# WirelessEarBuds_PhotoHall.net
KiCad netlist of a schematic drawn in Altium Designer
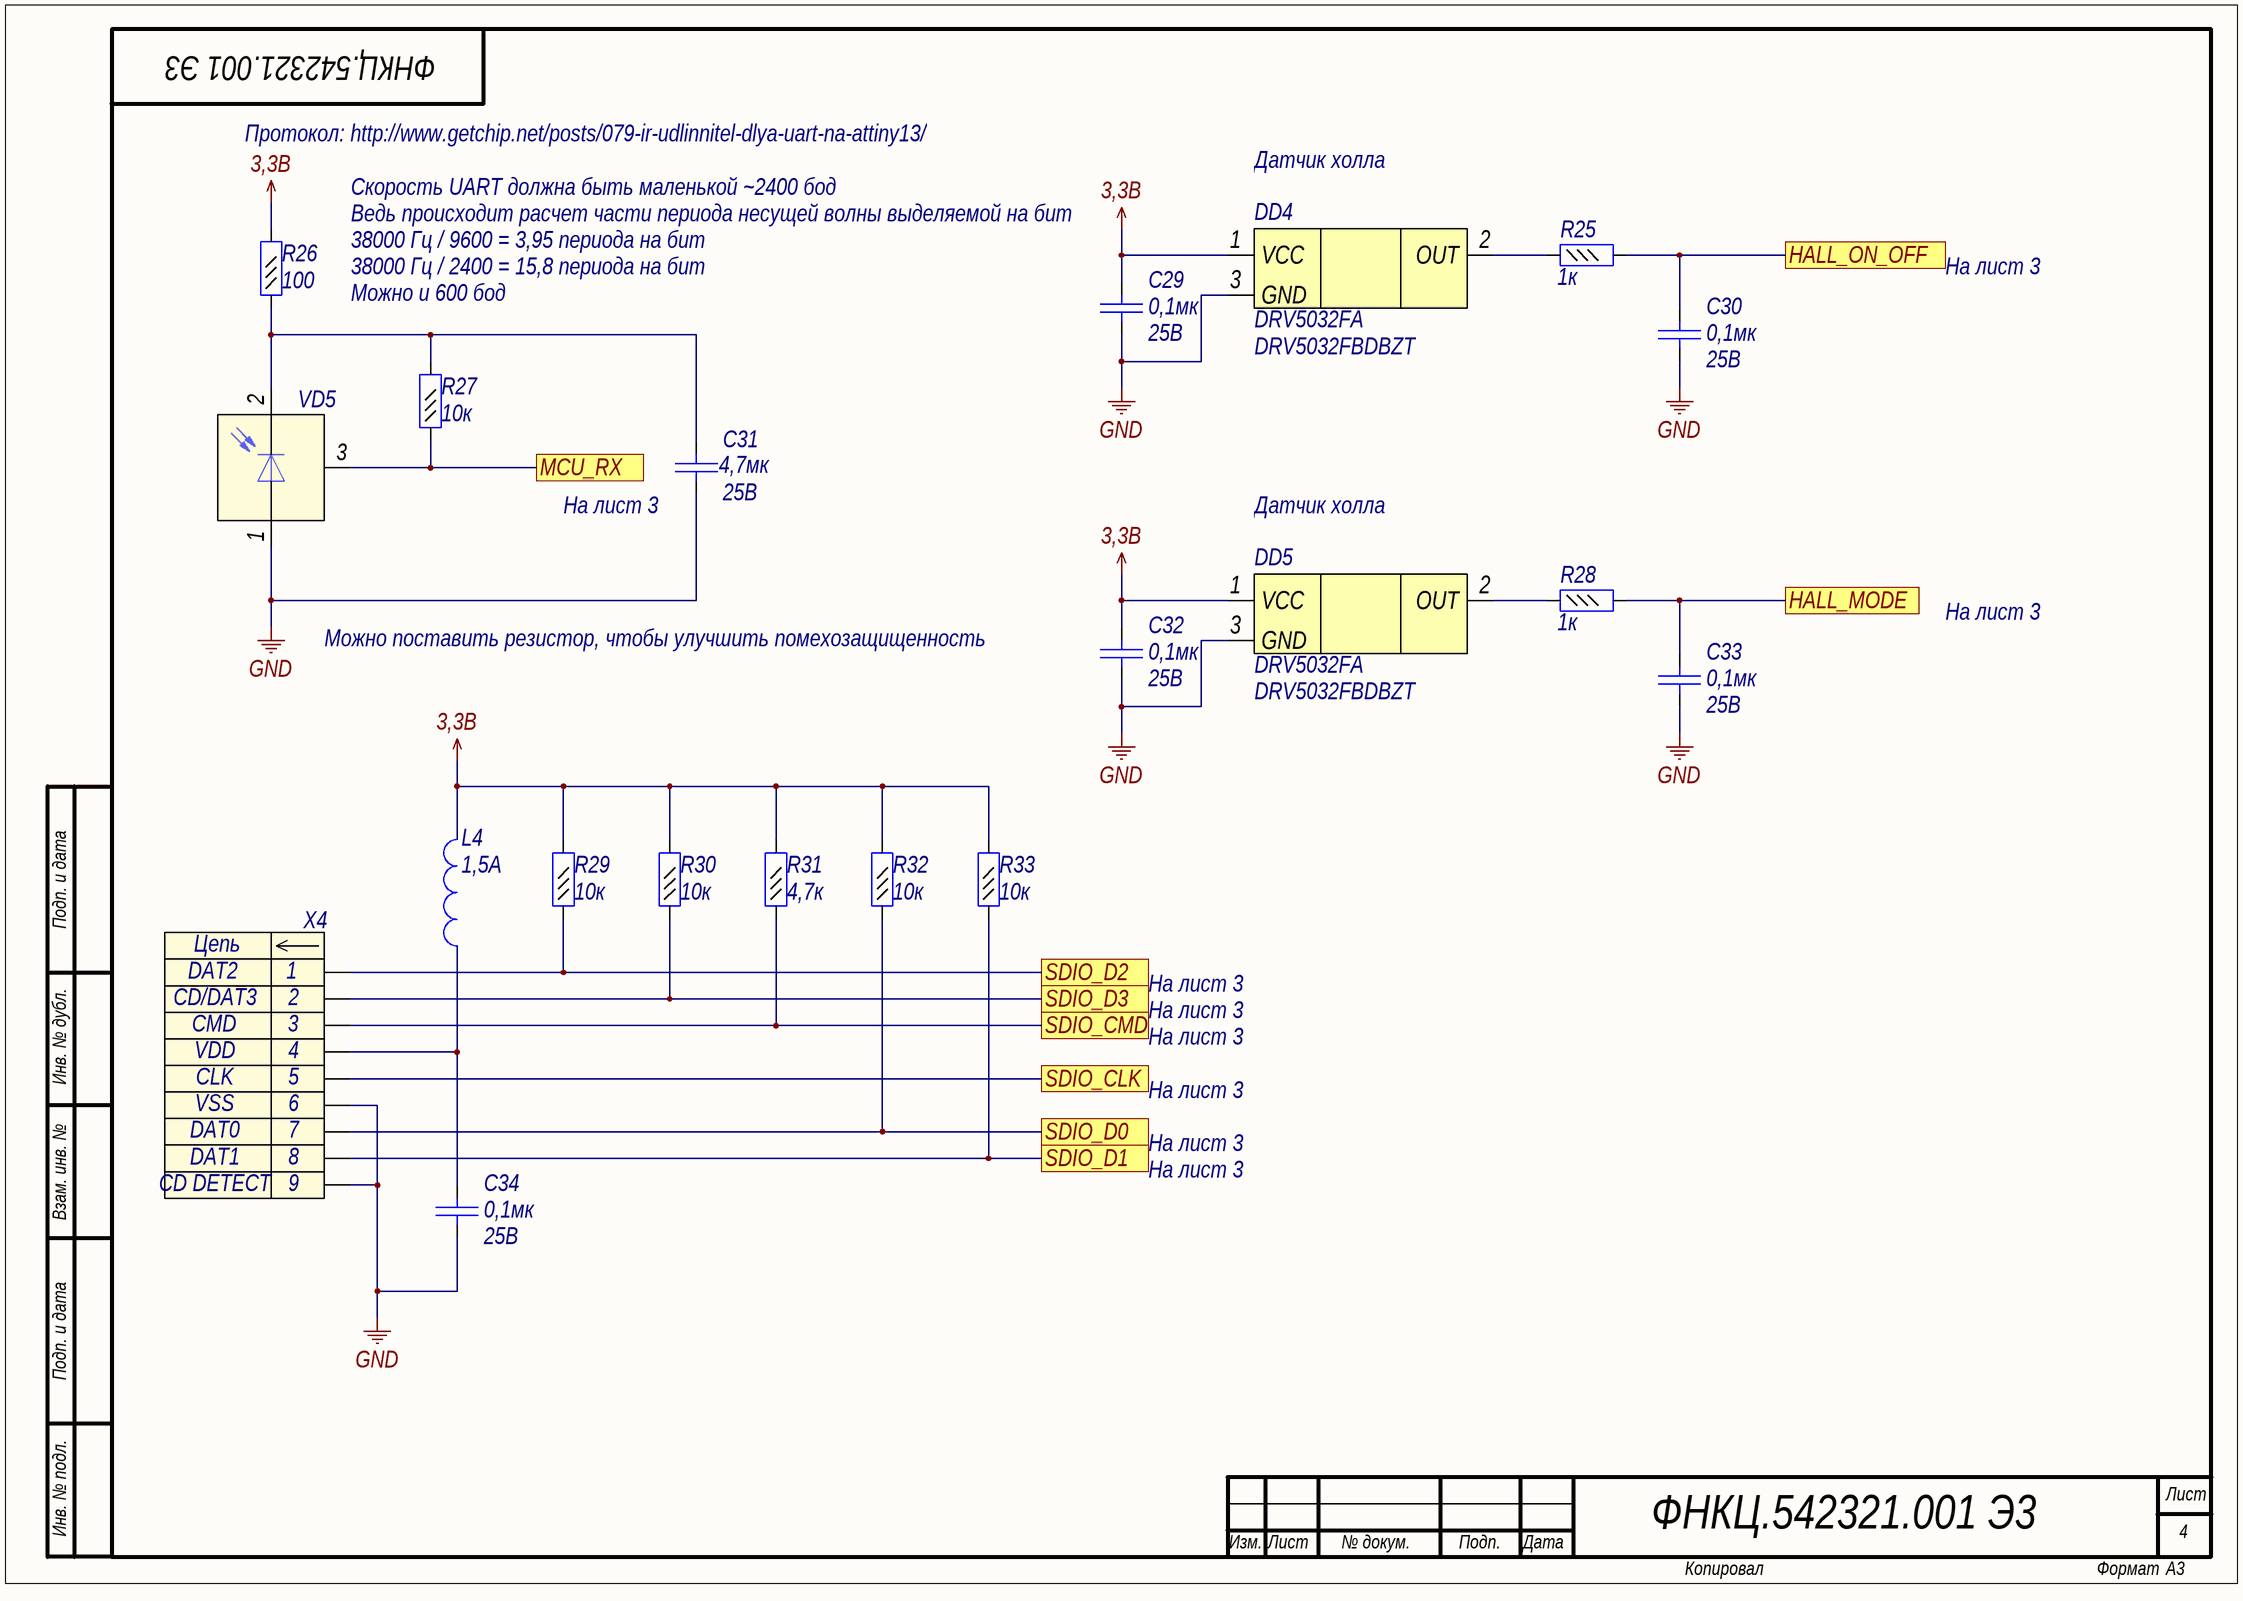
[diagram p0: WirelessEarBuds_PhotoHall.SchDoc]

(export (version "E")
  (design (tool "Eeschema 10.0.6"))
  (components
    (comp (ref "C29")
      (value "0,1мк")
      (footprint "C0402")
      (description "Конденсатор")
      (fields
        (field (name "VOLTAGE") "25B")
        (field (name "PART NUMBER") "GRM155F51E104Z**")
        (field (name "Comment") "Capacitor")
      )
      (libsource (lib "MOP44") (part "Capacitor"))
    )
    (comp (ref "C30")
      (value "0,1мк")
      (footprint "C0402")
      (description "Конденсатор")
      (fields
        (field (name "VOLTAGE") "25B")
        (field (name "PART NUMBER") "GRM155F51E104Z**")
        (field (name "Comment") "Capacitor")
      )
      (libsource (lib "MOP44") (part "Capacitor"))
    )
    (comp (ref "C31")
      (value "4,7мк")
      (footprint "C0805")
      (description "Конденсатор")
      (fields
        (field (name "VOLTAGE") "25B")
        (field (name "PART NUMBER") "GRM21BR61E475KA12L")
        (field (name "Comment") "Capacitor")
      )
      (libsource (lib "MOP44") (part "Capacitor"))
    )
    (comp (ref "C32")
      (value "0,1мк")
      (footprint "C0402")
      (description "Конденсатор")
      (fields
        (field (name "VOLTAGE") "25B")
        (field (name "PART NUMBER") "GRM155F51E104Z**")
        (field (name "Comment") "Capacitor")
      )
      (libsource (lib "MOP44") (part "Capacitor"))
    )
    (comp (ref "C33")
      (value "0,1мк")
      (footprint "C0402")
      (description "Конденсатор")
      (fields
        (field (name "VOLTAGE") "25B")
        (field (name "PART NUMBER") "GRM155F51E104Z**")
        (field (name "Comment") "Capacitor")
      )
      (libsource (lib "MOP44") (part "Capacitor"))
    )
    (comp (ref "C34")
      (value "0,1мк")
      (footprint "C0402")
      (description "Конденсатор")
      (fields
        (field (name "VOLTAGE") "25B")
        (field (name "PART NUMBER") "GRM155F51E104Z**")
        (field (name "Comment") "Capacitor")
      )
      (libsource (lib "MOP44") (part "Capacitor"))
    )
    (comp (ref "DD4")
      (value "DRV5032")
      (footprint "SOT23-3")
      (description "Датчик Холла с рекордно низким потреблением")
      (fields (field (name "PART NUMBER") "DRV5032FA"))
      (libsource (lib "MOP44") (part "DRV5032"))
    )
    (comp (ref "DD5")
      (value "DRV5032")
      (footprint "SOT23-3")
      (description "Датчик Холла с рекордно низким потреблением")
      (fields (field (name "PART NUMBER") "DRV5032FA"))
      (libsource (lib "MOP44") (part "DRV5032"))
    )
    (comp (ref "L4")
      (value "Inductor")
      (footprint "L0603")
      (description "EMI Suppression Filter")
      (fields (field (name "RATED CURRENT") "1,5A") (field (name "PART NUMBER") "BLM18PG181SN1D"))
      (libsource (lib "MOP44") (part "Inductor"))
    )
    (comp (ref "R25")
      (value "1к")
      (footprint "R0402")
      (description "Резистор")
      (fields (field (name "PART NUMBER") "RC0402FR-071KL") (field (name "POWER") "0,062Вт"))
      (libsource (lib "") (part "Resistor_0,062Вт_1"))
    )
    (comp (ref "R26")
      (value "100")
      (footprint "R0402")
      (description "Резистор")
      (fields (field (name "PART NUMBER") "RC0402FR-07100RL") (field (name "POWER") "0,062Вт"))
      (libsource (lib "MOP44") (part "Resistor_0,062Вт"))
    )
    (comp (ref "R27")
      (value "10к")
      (footprint "R0402")
      (description "Резистор")
      (fields (field (name "PART NUMBER") "RC0402FR-0710KL") (field (name "POWER") "0,062Вт"))
      (libsource (lib "MOP44") (part "Resistor_0,062Вт"))
    )
    (comp (ref "R28")
      (value "1к")
      (footprint "R0402")
      (description "Резистор")
      (fields (field (name "PART NUMBER") "RC0402FR-071KL") (field (name "POWER") "0,062Вт"))
      (libsource (lib "") (part "Resistor_0,062Вт_1"))
    )
    (comp (ref "R29")
      (value "10к")
      (footprint "R0402")
      (description "Резистор")
      (fields (field (name "PART NUMBER") "RC0402FR-0710KL") (field (name "POWER") "0,062Вт"))
      (libsource (lib "MOP44") (part "Resistor_0,062Вт"))
    )
    (comp (ref "R30")
      (value "10к")
      (footprint "R0402")
      (description "Резистор")
      (fields (field (name "PART NUMBER") "RC0402FR-0710KL") (field (name "POWER") "0,062Вт"))
      (libsource (lib "MOP44") (part "Resistor_0,062Вт"))
    )
    (comp (ref "R31")
      (value "4,7к")
      (footprint "R0402")
      (description "Резистор")
      (fields (field (name "PART NUMBER") "RC0402FR-074K7") (field (name "POWER") "0,062Вт"))
      (libsource (lib "MOP44") (part "Resistor_0,062Вт"))
    )
    (comp (ref "R32")
      (value "10к")
      (footprint "R0402")
      (description "Резистор")
      (fields (field (name "PART NUMBER") "RC0402FR-0710KL") (field (name "POWER") "0,062Вт"))
      (libsource (lib "MOP44") (part "Resistor_0,062Вт"))
    )
    (comp (ref "R33")
      (value "10к")
      (footprint "R0402")
      (description "Резистор")
      (fields (field (name "PART NUMBER") "RC0402FR-0710KL") (field (name "POWER") "0,062Вт"))
      (libsource (lib "MOP44") (part "Resistor_0,062Вт"))
    )
    (comp (ref "VD5")
      (value "IR_LED")
      (footprint "TVCAST")
      (description "Светодиод")
      (fields (field (name "PART NUMBER") "TSOP39238"))
      (libsource (lib "MOP44") (part "IR_LED"))
    )
    (comp (ref "X4")
      (value "MICROSD-SDIO")
      (footprint "MICROSD")
      (libsource (lib "MOP44") (part "MICROSD-SDIO"))
    )
  )
  (nets
    (net (code "1") (name "/HALL_MODE") (class "Default")
      (node (ref "C33") (pin "1") (pinfunction "1_1") (pintype "passive"))
      (node (ref "R28") (pin "2") (pinfunction "2_2") (pintype "passive"))
    )
    (net (code "2") (name "/HALL_ON_OFF") (class "Default")
      (node (ref "C30") (pin "1") (pinfunction "1_1") (pintype "passive"))
      (node (ref "R25") (pin "2") (pinfunction "2_2") (pintype "passive"))
    )
    (net (code "3") (name "/MCU_RX") (class "Default")
      (node (ref "R27") (pin "1") (pinfunction "1_1") (pintype "passive"))
      (node (ref "VD5") (pin "3") (pinfunction "OUT_3") (pintype "passive"))
    )
    (net (code "4") (name "/SDIO_CLK") (class "Default")
      (node (ref "X4") (pin "5") (pinfunction "5_5") (pintype "passive"))
    )
    (net (code "5") (name "/SDIO_CMD") (class "Default")
      (node (ref "R31") (pin "1") (pinfunction "1_1") (pintype "passive"))
      (node (ref "X4") (pin "3") (pinfunction "3_3") (pintype "passive"))
    )
    (net (code "6") (name "/SDIO_D0") (class "Default")
      (node (ref "R32") (pin "1") (pinfunction "1_1") (pintype "passive"))
      (node (ref "X4") (pin "7") (pinfunction "7_7") (pintype "passive"))
    )
    (net (code "7") (name "/SDIO_D1") (class "Default")
      (node (ref "R33") (pin "1") (pinfunction "1_1") (pintype "passive"))
      (node (ref "X4") (pin "8") (pinfunction "8_8") (pintype "passive"))
    )
    (net (code "8") (name "/SDIO_D2") (class "Default")
      (node (ref "R29") (pin "1") (pinfunction "1_1") (pintype "passive"))
      (node (ref "X4") (pin "1") (pinfunction "1_1") (pintype "passive"))
    )
    (net (code "9") (name "/SDIO_D3") (class "Default")
      (node (ref "R30") (pin "1") (pinfunction "1_1") (pintype "passive"))
      (node (ref "X4") (pin "2") (pinfunction "2_2") (pintype "passive"))
    )
    (net (code "10") (name "3,3B") (class "Default")
      (node (ref "C29") (pin "1") (pinfunction "1_1") (pintype "passive"))
      (node (ref "C32") (pin "1") (pinfunction "1_1") (pintype "passive"))
      (node (ref "DD4") (pin "1") (pinfunction "VCC_1") (pintype "passive"))
      (node (ref "DD5") (pin "1") (pinfunction "VCC_1") (pintype "passive"))
      (node (ref "L4") (pin "2") (pinfunction "2_2") (pintype "passive"))
      (node (ref "R26") (pin "2") (pinfunction "2_2") (pintype "passive"))
      (node (ref "R29") (pin "2") (pinfunction "2_2") (pintype "passive"))
      (node (ref "R30") (pin "2") (pinfunction "2_2") (pintype "passive"))
      (node (ref "R31") (pin "2") (pinfunction "2_2") (pintype "passive"))
      (node (ref "R32") (pin "2") (pinfunction "2_2") (pintype "passive"))
      (node (ref "R33") (pin "2") (pinfunction "2_2") (pintype "passive"))
    )
    (net (code "11") (name "GND") (class "Default")
      (node (ref "C29") (pin "2") (pinfunction "2_2") (pintype "passive"))
      (node (ref "C30") (pin "2") (pinfunction "2_2") (pintype "passive"))
      (node (ref "C31") (pin "1") (pinfunction "1_1") (pintype "passive"))
      (node (ref "C32") (pin "2") (pinfunction "2_2") (pintype "passive"))
      (node (ref "C33") (pin "2") (pinfunction "2_2") (pintype "passive"))
      (node (ref "C34") (pin "2") (pinfunction "2_2") (pintype "passive"))
      (node (ref "DD4") (pin "3") (pinfunction "GND_3") (pintype "passive"))
      (node (ref "DD5") (pin "3") (pinfunction "GND_3") (pintype "passive"))
      (node (ref "VD5") (pin "1") (pinfunction "GND_1") (pintype "passive"))
      (node (ref "X4") (pin "6") (pinfunction "6_6") (pintype "passive"))
      (node (ref "X4") (pin "9") (pinfunction "9_9") (pintype "passive"))
    )
    (net (code "12") (name "Net-(C34-Pad1)") (class "Default")
      (node (ref "C34") (pin "1") (pinfunction "1_1") (pintype "passive"))
      (node (ref "L4") (pin "1") (pinfunction "1_1") (pintype "passive"))
      (node (ref "X4") (pin "4") (pinfunction "4_4") (pintype "passive"))
    )
    (net (code "13") (name "Net-(DD4-OUT)") (class "Default")
      (node (ref "DD4") (pin "2") (pinfunction "OUT_2") (pintype "passive"))
      (node (ref "R25") (pin "1") (pinfunction "1_1") (pintype "passive"))
    )
    (net (code "14") (name "Net-(DD5-OUT)") (class "Default")
      (node (ref "DD5") (pin "2") (pinfunction "OUT_2") (pintype "passive"))
      (node (ref "R28") (pin "1") (pinfunction "1_1") (pintype "passive"))
    )
    (net (code "15") (name "Net-(VD5-VCC)") (class "Default")
      (node (ref "C31") (pin "2") (pinfunction "2_2") (pintype "passive"))
      (node (ref "R26") (pin "1") (pinfunction "1_1") (pintype "passive"))
      (node (ref "R27") (pin "2") (pinfunction "2_2") (pintype "passive"))
      (node (ref "VD5") (pin "2") (pinfunction "VCC_2") (pintype "passive"))
    )
  )
)
